# Sheet_1.net
KiCad netlist of a schematic drawn in EasyEDA
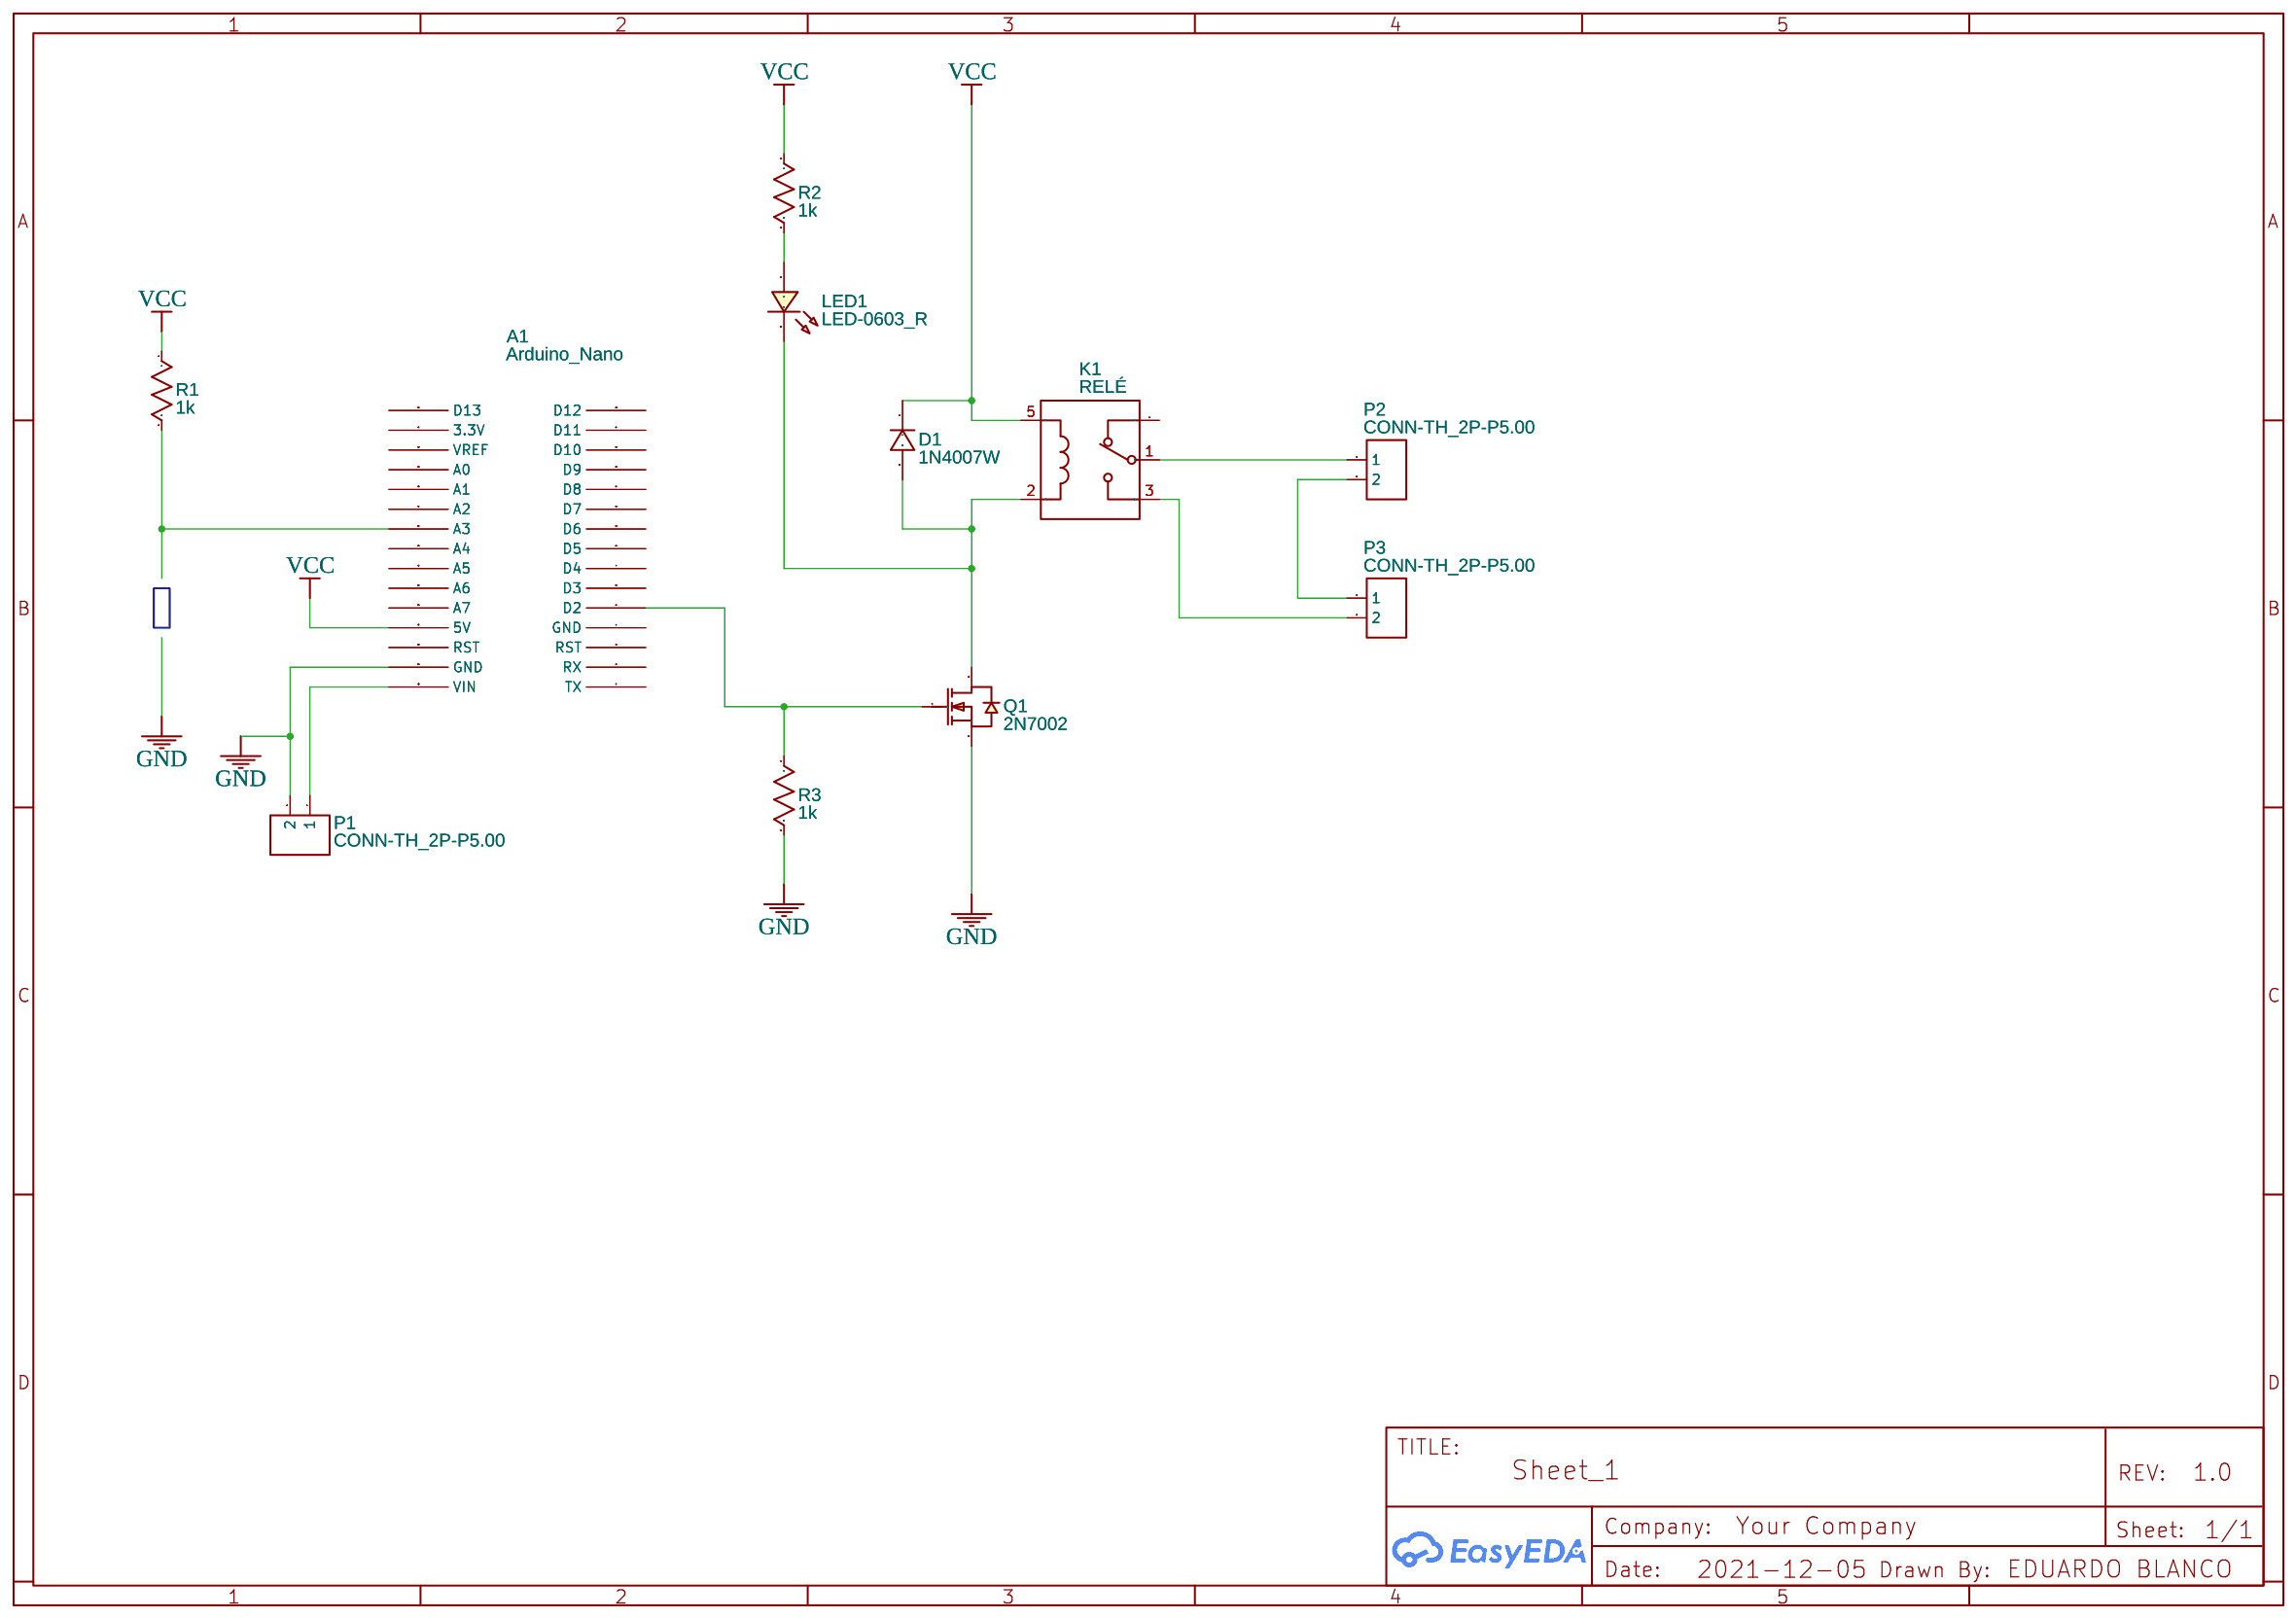
[diagram p0: schematic sheet]

(export (version "E")
  (design (tool "Eeschema 10.0.6"))
  (components
    (comp (ref "A1")
      (value "Arduino_Nano")
      (fields (field (name "BOM_Manufacturer Part") "Arduino Nano"))
      (libsource (lib "") (part "Unknown_250_-545"))
    )
    (comp (ref "D1")
      (value "1N4007W")
      (fields (field (name "BOM_Supplier Part") "C328592"))
      (libsource (lib "") (part "1N4007W"))
    )
    (comp (ref "K1") (value "RELÉ") (libsource (lib "") (part "RELÉ")))
    (comp (ref "LED1")
      (value "LED-0603_R")
      (fields
        (field (name "BOM_Manufacturer Part") "19-217/R6C-AL1M2VY/3T")
        (field (name "BOM_Supplier Part") "C72044")
      )
      (libsource (lib "") (part "LED-0603_R"))
    )
    (comp (ref "P1") (value "CONN-TH_2P-P5.00") (libsource (lib "") (part "CONN-TH_2P-P5.00_1")))
    (comp (ref "P2") (value "CONN-TH_2P-P5.00") (libsource (lib "") (part "CONN-TH_2P-P5.00")))
    (comp (ref "P3") (value "CONN-TH_2P-P5.00") (libsource (lib "") (part "CONN-TH_2P-P5.00")))
    (comp (ref "Q1")
      (value "2N7002")
      (fields (field (name "BOM_Manufacturer Part") "2N7002,215") (field (name "BOM_Supplier Part") "C65189"))
      (libsource (lib "") (part "2N7002"))
    )
    (comp (ref "R1") (value "1k") (libsource (lib "") (part "R_0603_US")))
    (comp (ref "R2") (value "1k") (libsource (lib "") (part "R_0603_US")))
    (comp (ref "R3") (value "1k") (libsource (lib "") (part "R_0603_US")))
  )
  (nets
    (net (code "1") (name "GND") (class "Default")
      (node (ref "A1") (pin "29") (pinfunction "GND_29") (pintype "unspecified"))
      (node (ref "P1") (pin "2") (pinfunction "2_2") (pintype "unspecified"))
      (node (ref "Q1") (pin "2") (pinfunction "S_2") (pintype "unspecified"))
      (node (ref "R3") (pin "2") (pinfunction "2_2") (pintype "unspecified"))
    )
    (net (code "2") (name "Net-(A1-A3)") (class "Default")
      (node (ref "A1") (pin "22") (pinfunction "A3_22") (pintype "unspecified"))
      (node (ref "R1") (pin "2") (pinfunction "2_2") (pintype "unspecified"))
    )
    (net (code "3") (name "Net-(A1-D2)") (class "Default")
      (node (ref "A1") (pin "5") (pinfunction "D2_5") (pintype "unspecified"))
      (node (ref "Q1") (pin "1") (pinfunction "G_1") (pintype "unspecified"))
      (node (ref "R3") (pin "1") (pinfunction "1_1") (pintype "unspecified"))
    )
    (net (code "4") (name "Net-(A1-VIN)") (class "Default")
      (node (ref "A1") (pin "30") (pinfunction "VIN_30") (pintype "unspecified"))
      (node (ref "P1") (pin "1") (pinfunction "1_1") (pintype "unspecified"))
    )
    (net (code "5") (name "Net-(K1-Pad1)") (class "Default")
      (node (ref "K1") (pin "1") (pinfunction "1_1") (pintype "unspecified"))
      (node (ref "P2") (pin "1") (pinfunction "1_1") (pintype "unspecified"))
    )
    (net (code "6") (name "Net-(K1-Pad3)") (class "Default")
      (node (ref "K1") (pin "3") (pinfunction "3_3") (pintype "unspecified"))
      (node (ref "P3") (pin "2") (pinfunction "2_2") (pintype "unspecified"))
    )
    (net (code "7") (name "Net-(LED1-Pad1)") (class "Default")
      (node (ref "LED1") (pin "1") (pinfunction "1_1") (pintype "unspecified"))
      (node (ref "R2") (pin "2") (pinfunction "2_2") (pintype "unspecified"))
    )
    (net (code "8") (name "Net-(P2-Pad2)") (class "Default")
      (node (ref "P2") (pin "2") (pinfunction "2_2") (pintype "unspecified"))
      (node (ref "P3") (pin "1") (pinfunction "1_1") (pintype "unspecified"))
    )
    (net (code "9") (name "Net-(Q1-D)") (class "Default")
      (node (ref "D1") (pin "2") (pinfunction "2_2") (pintype "unspecified"))
      (node (ref "K1") (pin "2") (pinfunction "2_2") (pintype "unspecified"))
      (node (ref "LED1") (pin "2") (pinfunction "2_2") (pintype "unspecified"))
      (node (ref "Q1") (pin "3") (pinfunction "D_3") (pintype "unspecified"))
    )
    (net (code "10") (name "VCC") (class "Default")
      (node (ref "A1") (pin "27") (pinfunction "5V_27") (pintype "unspecified"))
      (node (ref "D1") (pin "1") (pinfunction "1_1") (pintype "unspecified"))
      (node (ref "K1") (pin "5") (pinfunction "5_5") (pintype "unspecified"))
      (node (ref "R1") (pin "1") (pinfunction "1_1") (pintype "unspecified"))
      (node (ref "R2") (pin "1") (pinfunction "1_1") (pintype "unspecified"))
    )
    (net (code "11") (name "unconnected-(A1-3.3V-Pad17)") (class "Default")
      (node (ref "A1") (pin "17") (pinfunction "3.3V_17") (pintype "unspecified"))
    )
    (net (code "12") (name "unconnected-(A1-A0-Pad19)") (class "Default")
      (node (ref "A1") (pin "19") (pinfunction "A0_19") (pintype "unspecified"))
    )
    (net (code "13") (name "unconnected-(A1-A1-Pad20)") (class "Default")
      (node (ref "A1") (pin "20") (pinfunction "A1_20") (pintype "unspecified"))
    )
    (net (code "14") (name "unconnected-(A1-A2-Pad21)") (class "Default")
      (node (ref "A1") (pin "21") (pinfunction "A2_21") (pintype "unspecified"))
    )
    (net (code "15") (name "unconnected-(A1-A4-Pad23)") (class "Default")
      (node (ref "A1") (pin "23") (pinfunction "A4_23") (pintype "unspecified"))
    )
    (net (code "16") (name "unconnected-(A1-A5-Pad24)") (class "Default")
      (node (ref "A1") (pin "24") (pinfunction "A5_24") (pintype "unspecified"))
    )
    (net (code "17") (name "unconnected-(A1-A6-Pad25)") (class "Default")
      (node (ref "A1") (pin "25") (pinfunction "A6_25") (pintype "unspecified"))
    )
    (net (code "18") (name "unconnected-(A1-A7-Pad26)") (class "Default")
      (node (ref "A1") (pin "26") (pinfunction "A7_26") (pintype "unspecified"))
    )
    (net (code "19") (name "unconnected-(A1-D3-Pad6)") (class "Default")
      (node (ref "A1") (pin "6") (pinfunction "D3_6") (pintype "unspecified"))
    )
    (net (code "20") (name "unconnected-(A1-D4-Pad7)") (class "Default")
      (node (ref "A1") (pin "7") (pinfunction "D4_7") (pintype "unspecified"))
    )
    (net (code "21") (name "unconnected-(A1-D5-Pad8)") (class "Default")
      (node (ref "A1") (pin "8") (pinfunction "D5_8") (pintype "unspecified"))
    )
    (net (code "22") (name "unconnected-(A1-D6-Pad9)") (class "Default")
      (node (ref "A1") (pin "9") (pinfunction "D6_9") (pintype "unspecified"))
    )
    (net (code "23") (name "unconnected-(A1-D7-Pad10)") (class "Default")
      (node (ref "A1") (pin "10") (pinfunction "D7_10") (pintype "unspecified"))
    )
    (net (code "24") (name "unconnected-(A1-D8-Pad11)") (class "Default")
      (node (ref "A1") (pin "11") (pinfunction "D8_11") (pintype "unspecified"))
    )
    (net (code "25") (name "unconnected-(A1-D9-Pad12)") (class "Default")
      (node (ref "A1") (pin "12") (pinfunction "D9_12") (pintype "unspecified"))
    )
    (net (code "26") (name "unconnected-(A1-D10-Pad13)") (class "Default")
      (node (ref "A1") (pin "13") (pinfunction "D10_13") (pintype "unspecified"))
    )
    (net (code "27") (name "unconnected-(A1-D11-Pad14)") (class "Default")
      (node (ref "A1") (pin "14") (pinfunction "D11_14") (pintype "unspecified"))
    )
    (net (code "28") (name "unconnected-(A1-D12-Pad15)") (class "Default")
      (node (ref "A1") (pin "15") (pinfunction "D12_15") (pintype "unspecified"))
    )
    (net (code "29") (name "unconnected-(A1-D13-Pad16)") (class "Default")
      (node (ref "A1") (pin "16") (pinfunction "D13_16") (pintype "unspecified"))
    )
    (net (code "30") (name "unconnected-(A1-GND-Pad4)") (class "Default")
      (node (ref "A1") (pin "4") (pinfunction "GND_4") (pintype "unspecified"))
    )
    (net (code "31") (name "unconnected-(A1-RST-Pad3)") (class "Default")
      (node (ref "A1") (pin "3") (pinfunction "RST_3") (pintype "unspecified"))
    )
    (net (code "32") (name "unconnected-(A1-RST-Pad28)") (class "Default")
      (node (ref "A1") (pin "28") (pinfunction "RST_28") (pintype "unspecified"))
    )
    (net (code "33") (name "unconnected-(A1-RX-Pad2)") (class "Default")
      (node (ref "A1") (pin "2") (pinfunction "RX_2") (pintype "unspecified"))
    )
    (net (code "34") (name "unconnected-(A1-TX-Pad1)") (class "Default")
      (node (ref "A1") (pin "1") (pinfunction "TX_1") (pintype "unspecified"))
    )
    (net (code "35") (name "unconnected-(A1-VREF-Pad18)") (class "Default")
      (node (ref "A1") (pin "18") (pinfunction "VREF_18") (pintype "unspecified"))
    )
    (net (code "36") (name "unconnected-(K1-Pad4)") (class "Default")
      (node (ref "K1") (pin "4") (pinfunction "4_4") (pintype "unspecified"))
    )
  )
)
